# 1-Schematic_PedalBoard.net
KiCad netlist of a schematic drawn in EasyEDA
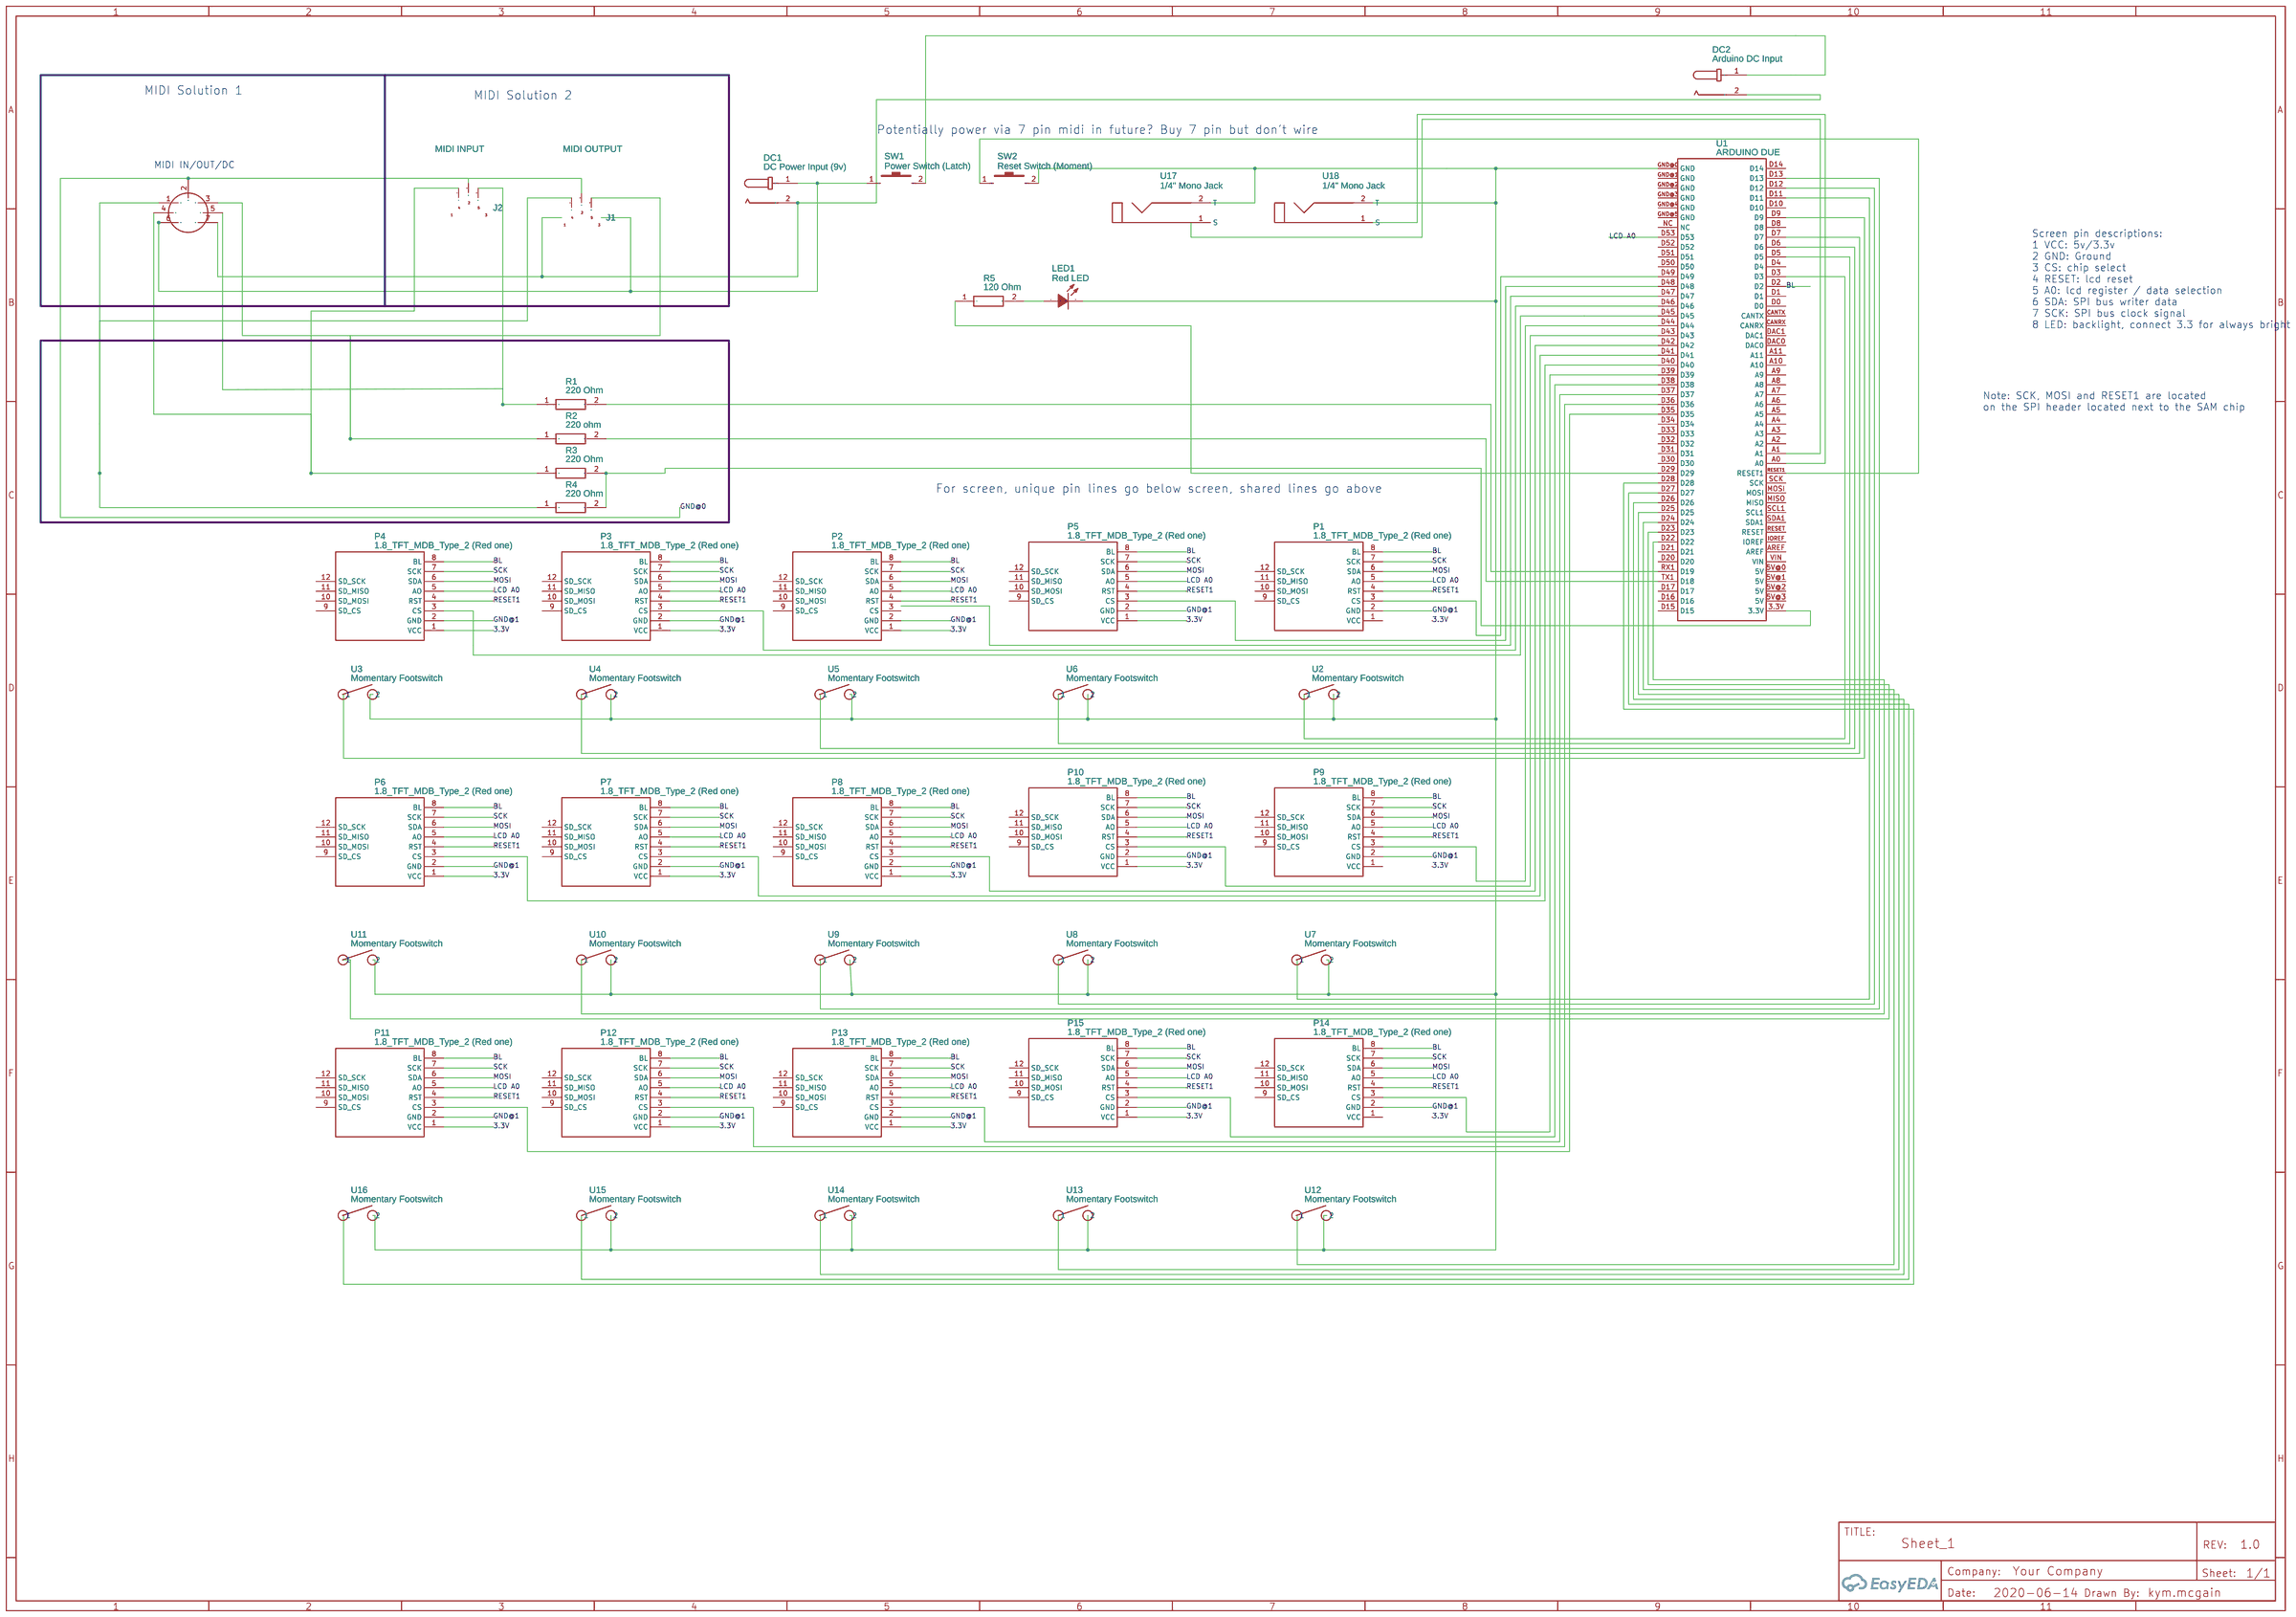
[diagram p0: Pedalboard]
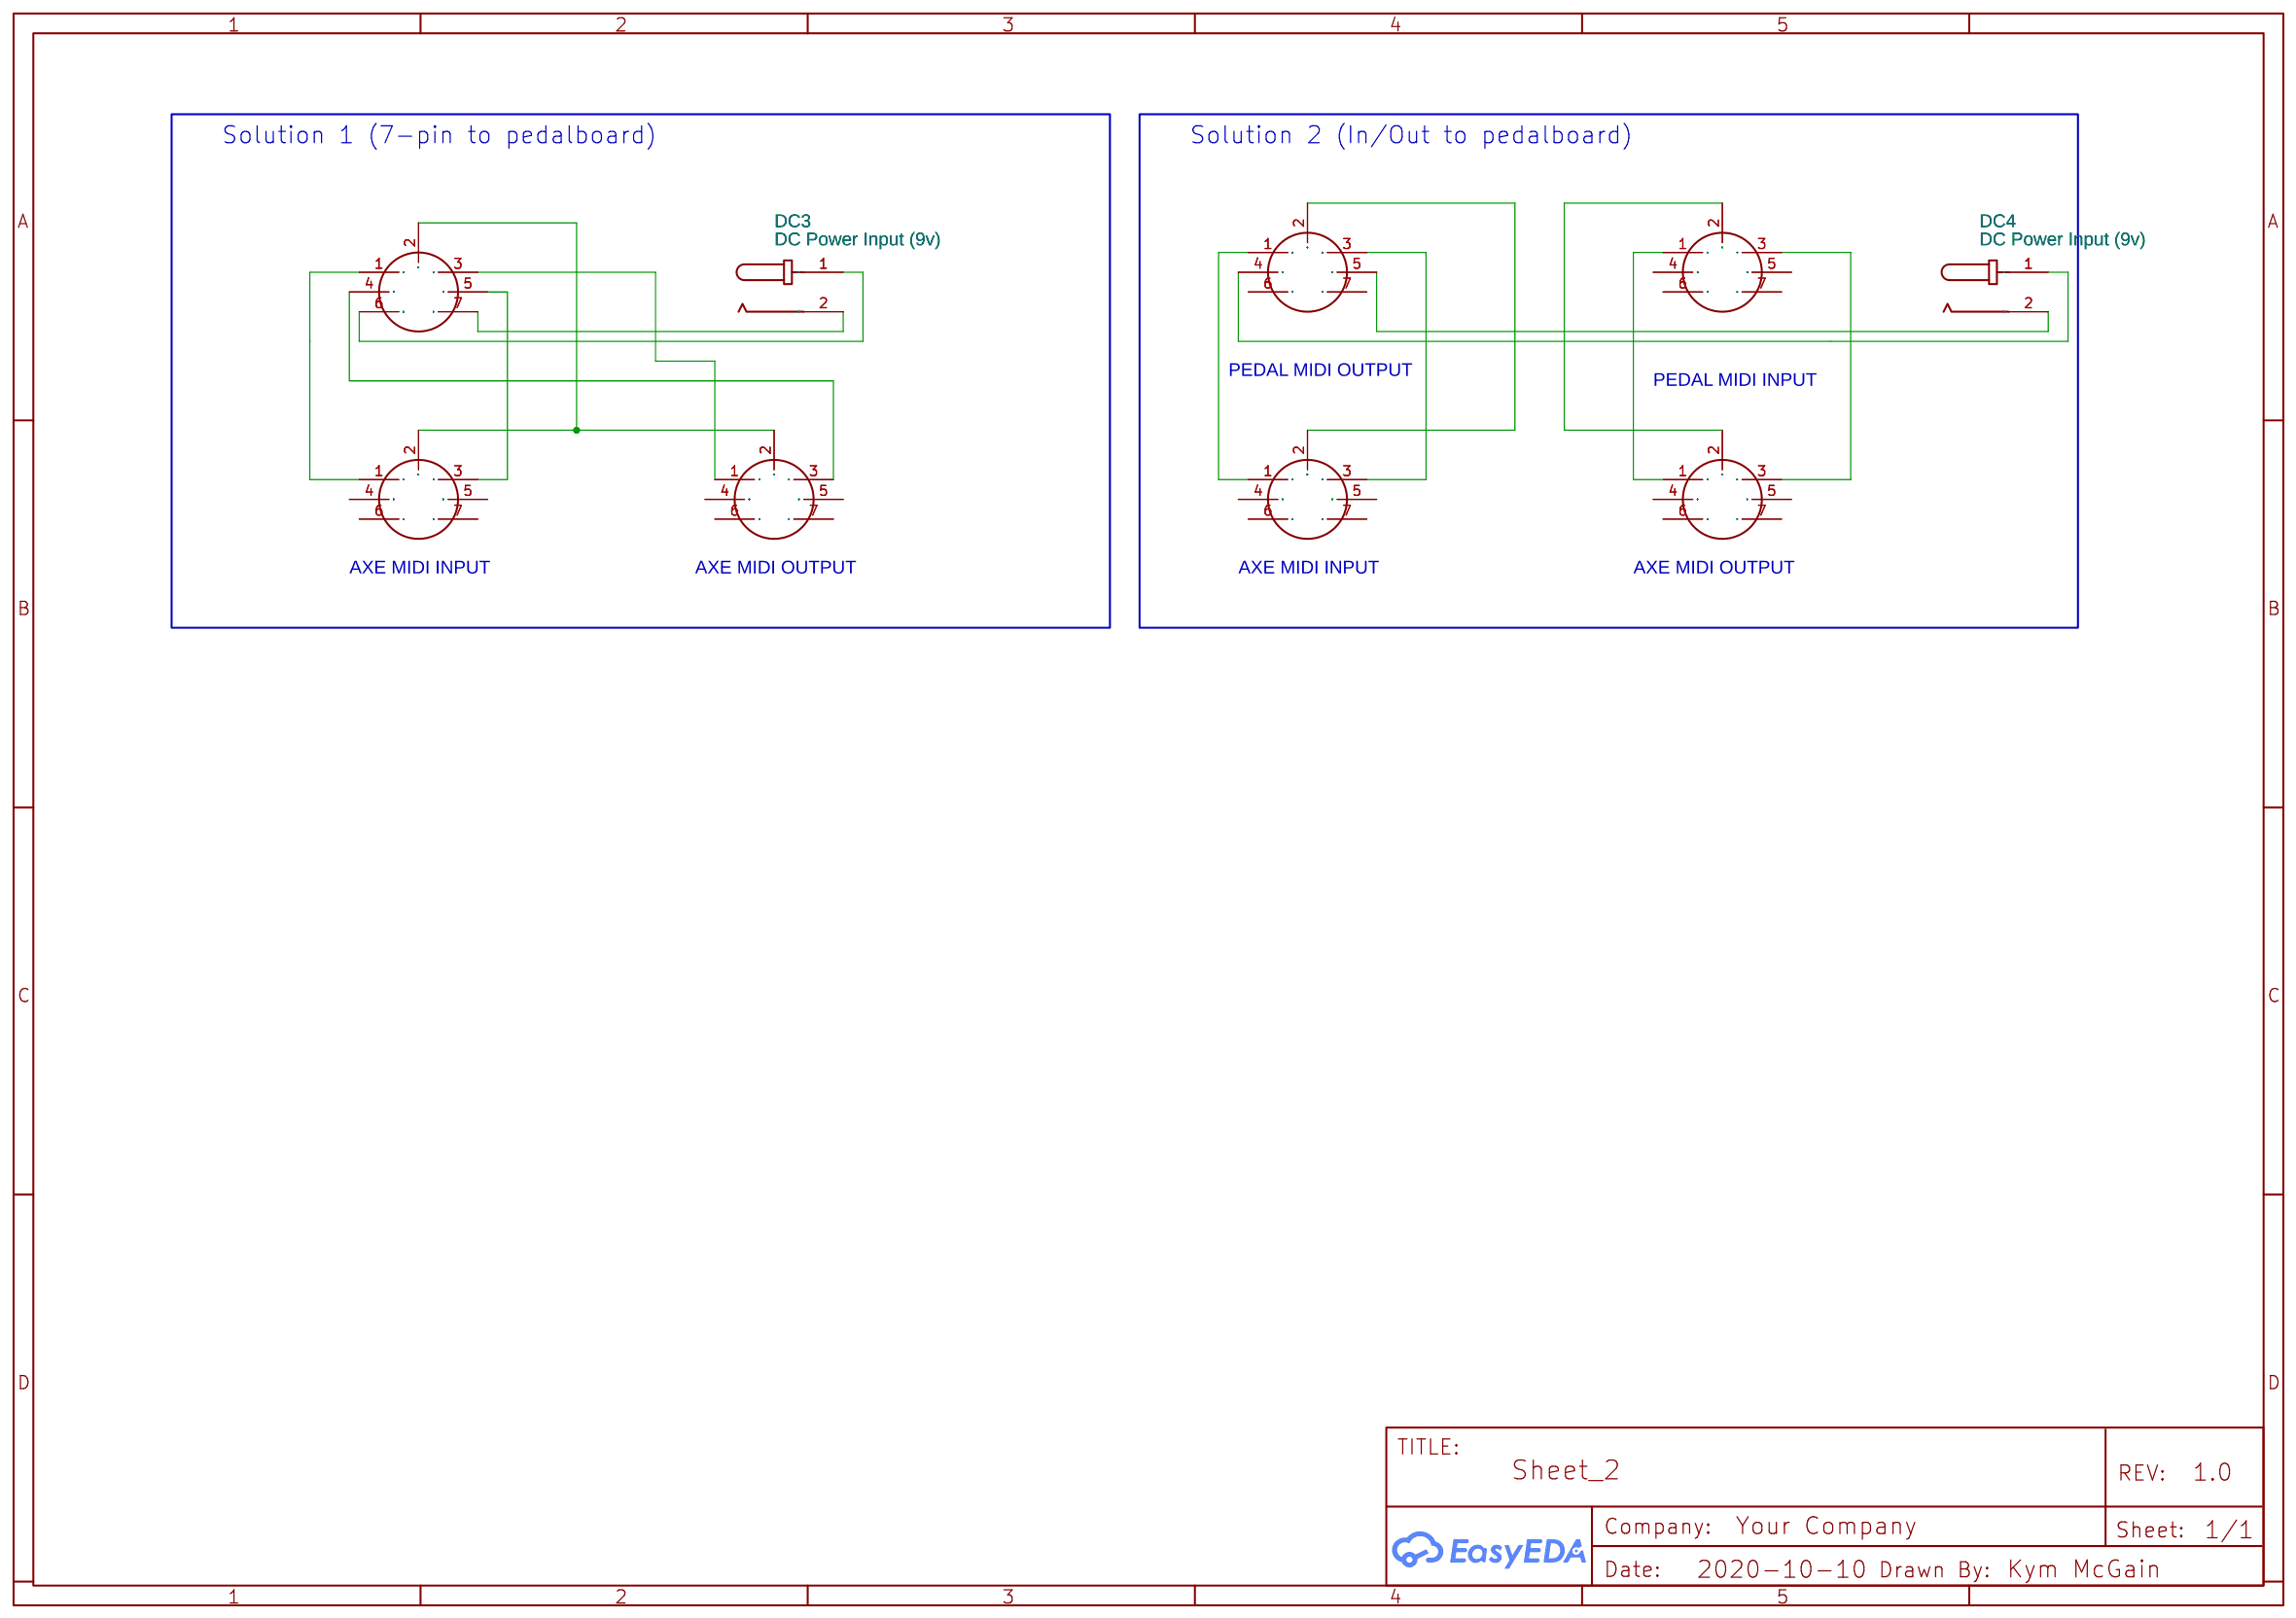
[diagram p1: MidiBox]

(export (version "E")
  (design (tool "Eeschema 10.0.6"))
  (components
    (comp (ref "DC1")
      (value "DC Power Input (9v)")
      (fields
        (field (name "BOM_Manufacturer Part") "DC-047B-13A")
        (field (name "BOM_Supplier Part") "C145923")
      )
      (libsource (lib "") (part "DC-047B-13A"))
    )
    (comp (ref "DC2")
      (value "Arduino DC Input")
      (fields
        (field (name "BOM_Manufacturer Part") "DC-047B-13A")
        (field (name "BOM_Supplier Part") "C145923")
      )
      (libsource (lib "") (part "DC-047B-13A"))
    )
    (comp (ref "J1") (value "MIDI OUTPUT") (libsource (lib "") (part "MIDI")))
    (comp (ref "J2") (value "MIDI INPUT") (libsource (lib "") (part "MIDI")))
    (comp (ref "LED1")
      (value "Red LED")
      (fields
        (field (name "BOM_Manufacturer Part") "KT-1206Red LED")
        (field (name "BOM_Supplier Part") "C49018")
      )
      (libsource (lib "") (part "KT-1206Red LED"))
    )
    (comp (ref "P1")
      (value "1.8_TFT_MDB_Type_2 (Red one)")
      (fields (field (name "BOM_Supplier Part") "undefined"))
      (libsource (lib "") (part "1.8_TFT_MDB_Type_2 (Red one)"))
    )
    (comp (ref "P2")
      (value "1.8_TFT_MDB_Type_2 (Red one)")
      (fields (field (name "BOM_Supplier Part") "undefined"))
      (libsource (lib "") (part "1.8_TFT_MDB_Type_2 (Red one)"))
    )
    (comp (ref "P3")
      (value "1.8_TFT_MDB_Type_2 (Red one)")
      (fields (field (name "BOM_Supplier Part") "undefined"))
      (libsource (lib "") (part "1.8_TFT_MDB_Type_2 (Red one)"))
    )
    (comp (ref "P4")
      (value "1.8_TFT_MDB_Type_2 (Red one)")
      (fields (field (name "BOM_Supplier Part") "undefined"))
      (libsource (lib "") (part "1.8_TFT_MDB_Type_2 (Red one)"))
    )
    (comp (ref "P5")
      (value "1.8_TFT_MDB_Type_2 (Red one)")
      (fields (field (name "BOM_Supplier Part") "undefined"))
      (libsource (lib "") (part "1.8_TFT_MDB_Type_2 (Red one)"))
    )
    (comp (ref "P6")
      (value "1.8_TFT_MDB_Type_2 (Red one)")
      (fields (field (name "BOM_Supplier Part") "undefined"))
      (libsource (lib "") (part "1.8_TFT_MDB_Type_2 (Red one)"))
    )
    (comp (ref "P7")
      (value "1.8_TFT_MDB_Type_2 (Red one)")
      (fields (field (name "BOM_Supplier Part") "undefined"))
      (libsource (lib "") (part "1.8_TFT_MDB_Type_2 (Red one)"))
    )
    (comp (ref "P8")
      (value "1.8_TFT_MDB_Type_2 (Red one)")
      (fields (field (name "BOM_Supplier Part") "undefined"))
      (libsource (lib "") (part "1.8_TFT_MDB_Type_2 (Red one)"))
    )
    (comp (ref "P9")
      (value "1.8_TFT_MDB_Type_2 (Red one)")
      (fields (field (name "BOM_Supplier Part") "undefined"))
      (libsource (lib "") (part "1.8_TFT_MDB_Type_2 (Red one)"))
    )
    (comp (ref "P10")
      (value "1.8_TFT_MDB_Type_2 (Red one)")
      (fields (field (name "BOM_Supplier Part") "undefined"))
      (libsource (lib "") (part "1.8_TFT_MDB_Type_2 (Red one)"))
    )
    (comp (ref "P11")
      (value "1.8_TFT_MDB_Type_2 (Red one)")
      (fields (field (name "BOM_Supplier Part") "undefined"))
      (libsource (lib "") (part "1.8_TFT_MDB_Type_2 (Red one)"))
    )
    (comp (ref "P12")
      (value "1.8_TFT_MDB_Type_2 (Red one)")
      (fields (field (name "BOM_Supplier Part") "undefined"))
      (libsource (lib "") (part "1.8_TFT_MDB_Type_2 (Red one)"))
    )
    (comp (ref "P13")
      (value "1.8_TFT_MDB_Type_2 (Red one)")
      (fields (field (name "BOM_Supplier Part") "undefined"))
      (libsource (lib "") (part "1.8_TFT_MDB_Type_2 (Red one)"))
    )
    (comp (ref "P14")
      (value "1.8_TFT_MDB_Type_2 (Red one)")
      (fields (field (name "BOM_Supplier Part") "undefined"))
      (libsource (lib "") (part "1.8_TFT_MDB_Type_2 (Red one)"))
    )
    (comp (ref "P15")
      (value "1.8_TFT_MDB_Type_2 (Red one)")
      (fields (field (name "BOM_Supplier Part") "undefined"))
      (libsource (lib "") (part "1.8_TFT_MDB_Type_2 (Red one)"))
    )
    (comp (ref "R1")
      (value "220 Ohm")
      (libsource (lib "") (part "200 Ohms ±5% 1W Chip Resistor 2512 CRCW2512200RJNTG"))
    )
    (comp (ref "R2")
      (value "220 ohm")
      (libsource (lib "") (part "200 Ohms ±5% 1W Chip Resistor 2512 CRCW2512200RJNTG"))
    )
    (comp (ref "R3")
      (value "220 Ohm")
      (libsource (lib "") (part "200 Ohms ±5% 1W Chip Resistor 2512 CRCW2512200RJNTG"))
    )
    (comp (ref "R4")
      (value "220 Ohm")
      (libsource (lib "") (part "200 Ohms ±5% 1W Chip Resistor 2512 CRCW2512200RJNTG"))
    )
    (comp (ref "R5")
      (value "120 Ohm")
      (libsource (lib "") (part "200 Ohms ±5% 1W Chip Resistor 2512 CRCW2512200RJNTG"))
    )
    (comp (ref "SW1")
      (value "Power Switch (Latch)")
      (fields
        (field (name "BOM_Manufacturer Part") "Switch3x4x2")
        (field (name "BOM_Supplier Part") "C26638")
      )
      (libsource (lib "") (part "Switch3x4x2"))
    )
    (comp (ref "SW2")
      (value "Reset Switch (Moment)")
      (fields
        (field (name "BOM_Manufacturer Part") "Switch3x4x2")
        (field (name "BOM_Supplier Part") "C26638")
      )
      (libsource (lib "") (part "Switch3x4x2"))
    )
    (comp (ref "U1") (value "ARDUINO DUE") (libsource (lib "") (part "ARDUINO DUE")))
    (comp (ref "U2") (value "Momentary Footswitch") (libsource (lib "") (part "Momentary Footswitch")))
    (comp (ref "U3") (value "Momentary Footswitch") (libsource (lib "") (part "Momentary Footswitch_1")))
    (comp (ref "U4") (value "Momentary Footswitch") (libsource (lib "") (part "Momentary Footswitch")))
    (comp (ref "U5") (value "Momentary Footswitch") (libsource (lib "") (part "Momentary Footswitch_1")))
    (comp (ref "U6") (value "Momentary Footswitch") (libsource (lib "") (part "Momentary Footswitch")))
    (comp (ref "U7") (value "Momentary Footswitch") (libsource (lib "") (part "Momentary Footswitch_1")))
    (comp (ref "U8") (value "Momentary Footswitch") (libsource (lib "") (part "Momentary Footswitch")))
    (comp (ref "U9") (value "Momentary Footswitch") (libsource (lib "") (part "Momentary Footswitch_1")))
    (comp (ref "U10") (value "Momentary Footswitch") (libsource (lib "") (part "Momentary Footswitch")))
    (comp (ref "U11") (value "Momentary Footswitch") (libsource (lib "") (part "Momentary Footswitch_1")))
    (comp (ref "U12") (value "Momentary Footswitch") (libsource (lib "") (part "Momentary Footswitch_1")))
    (comp (ref "U13") (value "Momentary Footswitch") (libsource (lib "") (part "Momentary Footswitch")))
    (comp (ref "U14") (value "Momentary Footswitch") (libsource (lib "") (part "Momentary Footswitch_1")))
    (comp (ref "U15") (value "Momentary Footswitch") (libsource (lib "") (part "Momentary Footswitch")))
    (comp (ref "U16") (value "Momentary Footswitch") (libsource (lib "") (part "Momentary Footswitch_1")))
    (comp (ref "U17")
      (value "1/4\" Mono Jack")
      (fields
        (field (name "BOM_Manufacturer Part") "NYS2162-U")
        (field (name "BOM_Supplier Part") "568-NYS2162-U")
      )
      (libsource (lib "") (part "1/4{dblquote} Mono Jack"))
    )
    (comp (ref "U18")
      (value "1/4\" Mono Jack")
      (fields
        (field (name "BOM_Manufacturer Part") "NYS2162-U")
        (field (name "BOM_Supplier Part") "568-NYS2162-U")
      )
      (libsource (lib "") (part "1/4{dblquote} Mono Jack"))
    )
    (comp (ref "U19") (value "DIN 45329") (libsource (lib "") (part "DIN 45329")))
    (comp (ref "DC3")
      (value "DC Power Input (9v)")
      (fields
        (field (name "BOM_Manufacturer Part") "DC-047B-13A")
        (field (name "BOM_Supplier Part") "C145923")
      )
      (libsource (lib "") (part "DC-047B-13A"))
    )
    (comp (ref "DC4")
      (value "DC Power Input (9v)")
      (fields
        (field (name "BOM_Manufacturer Part") "DC-047B-13A")
        (field (name "BOM_Supplier Part") "C145923")
      )
      (libsource (lib "") (part "DC-047B-13A"))
    )
    (comp (ref "U20") (value "DIN 45329") (libsource (lib "") (part "DIN 45329")))
    (comp (ref "U21") (value "DIN 45329") (libsource (lib "") (part "DIN 45329")))
    (comp (ref "U22") (value "DIN 45329") (libsource (lib "") (part "DIN 45329")))
    (comp (ref "U23") (value "DIN 45329") (libsource (lib "") (part "DIN 45329")))
    (comp (ref "U24") (value "DIN 45329") (libsource (lib "") (part "DIN 45329")))
    (comp (ref "U25") (value "DIN 45329") (libsource (lib "") (part "DIN 45329")))
    (comp (ref "U26") (value "DIN 45329") (libsource (lib "") (part "DIN 45329")))
  )
  (nets
    (net (code "1") (name "3.3V") (class "Default")
      (node (ref "P10") (pin "1") (pinfunction "VCC_1") (pintype "unspecified"))
      (node (ref "P11") (pin "1") (pinfunction "VCC_1") (pintype "unspecified"))
      (node (ref "P12") (pin "1") (pinfunction "VCC_1") (pintype "unspecified"))
      (node (ref "P13") (pin "1") (pinfunction "VCC_1") (pintype "unspecified"))
      (node (ref "P15") (pin "1") (pinfunction "VCC_1") (pintype "unspecified"))
      (node (ref "P2") (pin "1") (pinfunction "VCC_1") (pintype "unspecified"))
      (node (ref "P3") (pin "1") (pinfunction "VCC_1") (pintype "unspecified"))
      (node (ref "P4") (pin "1") (pinfunction "VCC_1") (pintype "unspecified"))
      (node (ref "P5") (pin "1") (pinfunction "VCC_1") (pintype "unspecified"))
      (node (ref "P6") (pin "1") (pinfunction "VCC_1") (pintype "unspecified"))
      (node (ref "P7") (pin "1") (pinfunction "VCC_1") (pintype "unspecified"))
      (node (ref "P8") (pin "1") (pinfunction "VCC_1") (pintype "unspecified"))
    )
    (net (code "2") (name "BL") (class "Default")
      (node (ref "P1") (pin "8") (pinfunction "BL_8") (pintype "unspecified"))
      (node (ref "P10") (pin "8") (pinfunction "BL_8") (pintype "unspecified"))
      (node (ref "P11") (pin "8") (pinfunction "BL_8") (pintype "unspecified"))
      (node (ref "P12") (pin "8") (pinfunction "BL_8") (pintype "unspecified"))
      (node (ref "P13") (pin "8") (pinfunction "BL_8") (pintype "unspecified"))
      (node (ref "P14") (pin "8") (pinfunction "BL_8") (pintype "unspecified"))
      (node (ref "P15") (pin "8") (pinfunction "BL_8") (pintype "unspecified"))
      (node (ref "P2") (pin "8") (pinfunction "BL_8") (pintype "unspecified"))
      (node (ref "P3") (pin "8") (pinfunction "BL_8") (pintype "unspecified"))
      (node (ref "P4") (pin "8") (pinfunction "BL_8") (pintype "unspecified"))
      (node (ref "P5") (pin "8") (pinfunction "BL_8") (pintype "unspecified"))
      (node (ref "P6") (pin "8") (pinfunction "BL_8") (pintype "unspecified"))
      (node (ref "P7") (pin "8") (pinfunction "BL_8") (pintype "unspecified"))
      (node (ref "P8") (pin "8") (pinfunction "BL_8") (pintype "unspecified"))
      (node (ref "P9") (pin "8") (pinfunction "BL_8") (pintype "unspecified"))
      (node (ref "U1") (pin "D2") (pinfunction "D2_D2") (pintype "unspecified"))
    )
    (net (code "3") (name "GND@0") (class "Default")
      (node (ref "J1") (pin "R") (pinfunction "2_R") (pintype "bidirectional"))
      (node (ref "J2") (pin "R") (pinfunction "2_R") (pintype "bidirectional"))
      (node (ref "U19") (pin "2") (pinfunction "6_2") (pintype "unspecified"))
    )
    (net (code "4") (name "GND@1") (class "Default")
      (node (ref "P1") (pin "2") (pinfunction "GND_2") (pintype "unspecified"))
      (node (ref "P10") (pin "2") (pinfunction "GND_2") (pintype "unspecified"))
      (node (ref "P11") (pin "2") (pinfunction "GND_2") (pintype "unspecified"))
      (node (ref "P12") (pin "2") (pinfunction "GND_2") (pintype "unspecified"))
      (node (ref "P13") (pin "2") (pinfunction "GND_2") (pintype "unspecified"))
      (node (ref "P14") (pin "2") (pinfunction "GND_2") (pintype "unspecified"))
      (node (ref "P15") (pin "2") (pinfunction "GND_2") (pintype "unspecified"))
      (node (ref "P2") (pin "2") (pinfunction "GND_2") (pintype "unspecified"))
      (node (ref "P3") (pin "2") (pinfunction "GND_2") (pintype "unspecified"))
      (node (ref "P4") (pin "2") (pinfunction "GND_2") (pintype "unspecified"))
      (node (ref "P5") (pin "2") (pinfunction "GND_2") (pintype "unspecified"))
      (node (ref "P6") (pin "2") (pinfunction "GND_2") (pintype "unspecified"))
      (node (ref "P7") (pin "2") (pinfunction "GND_2") (pintype "unspecified"))
      (node (ref "P8") (pin "2") (pinfunction "GND_2") (pintype "unspecified"))
      (node (ref "P9") (pin "2") (pinfunction "GND_2") (pintype "unspecified"))
    )
    (net (code "5") (name "LCD A0") (class "Default")
      (node (ref "P1") (pin "5") (pinfunction "AO_5") (pintype "unspecified"))
      (node (ref "P10") (pin "5") (pinfunction "AO_5") (pintype "unspecified"))
      (node (ref "P11") (pin "5") (pinfunction "AO_5") (pintype "unspecified"))
      (node (ref "P12") (pin "5") (pinfunction "AO_5") (pintype "unspecified"))
      (node (ref "P13") (pin "5") (pinfunction "AO_5") (pintype "unspecified"))
      (node (ref "P14") (pin "5") (pinfunction "AO_5") (pintype "unspecified"))
      (node (ref "P15") (pin "5") (pinfunction "AO_5") (pintype "unspecified"))
      (node (ref "P2") (pin "5") (pinfunction "AO_5") (pintype "unspecified"))
      (node (ref "P3") (pin "5") (pinfunction "AO_5") (pintype "unspecified"))
      (node (ref "P4") (pin "5") (pinfunction "AO_5") (pintype "unspecified"))
      (node (ref "P5") (pin "5") (pinfunction "AO_5") (pintype "unspecified"))
      (node (ref "P6") (pin "5") (pinfunction "AO_5") (pintype "unspecified"))
      (node (ref "P7") (pin "5") (pinfunction "AO_5") (pintype "unspecified"))
      (node (ref "P8") (pin "5") (pinfunction "AO_5") (pintype "unspecified"))
      (node (ref "P9") (pin "5") (pinfunction "AO_5") (pintype "unspecified"))
      (node (ref "U1") (pin "D53") (pinfunction "D53_D53") (pintype "unspecified"))
    )
    (net (code "6") (name "MOSI") (class "Default")
      (node (ref "P1") (pin "6") (pinfunction "SDA_6") (pintype "unspecified"))
      (node (ref "P10") (pin "6") (pinfunction "SDA_6") (pintype "unspecified"))
      (node (ref "P11") (pin "6") (pinfunction "SDA_6") (pintype "unspecified"))
      (node (ref "P12") (pin "6") (pinfunction "SDA_6") (pintype "unspecified"))
      (node (ref "P13") (pin "6") (pinfunction "SDA_6") (pintype "unspecified"))
      (node (ref "P14") (pin "6") (pinfunction "SDA_6") (pintype "unspecified"))
      (node (ref "P15") (pin "6") (pinfunction "SDA_6") (pintype "unspecified"))
      (node (ref "P2") (pin "6") (pinfunction "SDA_6") (pintype "unspecified"))
      (node (ref "P3") (pin "6") (pinfunction "SDA_6") (pintype "unspecified"))
      (node (ref "P4") (pin "6") (pinfunction "SDA_6") (pintype "unspecified"))
      (node (ref "P5") (pin "6") (pinfunction "SDA_6") (pintype "unspecified"))
      (node (ref "P6") (pin "6") (pinfunction "SDA_6") (pintype "unspecified"))
      (node (ref "P7") (pin "6") (pinfunction "SDA_6") (pintype "unspecified"))
      (node (ref "P8") (pin "6") (pinfunction "SDA_6") (pintype "unspecified"))
      (node (ref "P9") (pin "6") (pinfunction "SDA_6") (pintype "unspecified"))
    )
    (net (code "7") (name "Net-(DC1-Pad1)") (class "Default")
      (node (ref "DC1") (pin "1") (pinfunction "1_1") (pintype "unspecified"))
      (node (ref "SW1") (pin "1") (pinfunction "1_1") (pintype "input"))
      (node (ref "U19") (pin "6") (pinfunction "6_6") (pintype "unspecified"))
    )
    (net (code "8") (name "Net-(DC1-Pad2)") (class "Default")
      (node (ref "DC1") (pin "2") (pinfunction "2_2") (pintype "unspecified"))
      (node (ref "DC2") (pin "2") (pinfunction "2_2") (pintype "unspecified"))
      (node (ref "U19") (pin "7") (pinfunction "6_7") (pintype "unspecified"))
    )
    (net (code "9") (name "Net-(DC2-Pad1)") (class "Default")
      (node (ref "DC2") (pin "1") (pinfunction "1_1") (pintype "unspecified"))
      (node (ref "SW1") (pin "2") (pinfunction "2_2") (pintype "input"))
    )
    (net (code "10") (name "Net-(DC3-Pad1)") (class "Default")
      (node (ref "DC3") (pin "1") (pinfunction "1_1") (pintype "unspecified"))
      (node (ref "U20") (pin "6") (pinfunction "6_6") (pintype "unspecified"))
    )
    (net (code "11") (name "Net-(DC3-Pad2)") (class "Default")
      (node (ref "DC3") (pin "2") (pinfunction "2_2") (pintype "unspecified"))
      (node (ref "U20") (pin "7") (pinfunction "6_7") (pintype "unspecified"))
    )
    (net (code "12") (name "Net-(DC4-Pad1)") (class "Default")
      (node (ref "DC4") (pin "1") (pinfunction "1_1") (pintype "unspecified"))
      (node (ref "U25") (pin "4") (pinfunction "6_4") (pintype "unspecified"))
    )
    (net (code "13") (name "Net-(DC4-Pad2)") (class "Default")
      (node (ref "DC4") (pin "2") (pinfunction "2_2") (pintype "unspecified"))
      (node (ref "U25") (pin "5") (pinfunction "6_5") (pintype "unspecified"))
    )
    (net (code "14") (name "Net-(J1-4)") (class "Default")
      (node (ref "J1") (pin "T") (pinfunction "4_T") (pintype "bidirectional"))
      (node (ref "R4") (pin "1") (pinfunction "1_1") (pintype "bidirectional"))
      (node (ref "U19") (pin "1") (pinfunction "6_1") (pintype "unspecified"))
    )
    (net (code "15") (name "Net-(J1-5)") (class "Default")
      (node (ref "J1") (pin "S") (pinfunction "5_S") (pintype "bidirectional"))
      (node (ref "R2") (pin "1") (pinfunction "1_1") (pintype "bidirectional"))
      (node (ref "U19") (pin "3") (pinfunction "6_3") (pintype "unspecified"))
    )
    (net (code "16") (name "Net-(J2-4)") (class "Default")
      (node (ref "J2") (pin "T") (pinfunction "4_T") (pintype "bidirectional"))
      (node (ref "R3") (pin "1") (pinfunction "1_1") (pintype "bidirectional"))
      (node (ref "U19") (pin "4") (pinfunction "6_4") (pintype "unspecified"))
    )
    (net (code "17") (name "Net-(J2-5)") (class "Default")
      (node (ref "J2") (pin "S") (pinfunction "5_S") (pintype "bidirectional"))
      (node (ref "R1") (pin "1") (pinfunction "1_1") (pintype "bidirectional"))
      (node (ref "U19") (pin "5") (pinfunction "6_5") (pintype "unspecified"))
    )
    (net (code "18") (name "Net-(LED1-A)") (class "Default")
      (node (ref "LED1") (pin "1") (pinfunction "A_1") (pintype "unspecified"))
      (node (ref "R5") (pin "2") (pinfunction "2_2") (pintype "bidirectional"))
    )
    (net (code "19") (name "Net-(LED1-K)") (class "Default")
      (node (ref "LED1") (pin "2") (pinfunction "K_2") (pintype "unspecified"))
      (node (ref "SW2") (pin "2") (pinfunction "2_2") (pintype "input"))
      (node (ref "U1") (pin "GND@0") (pinfunction "GND_GND@0") (pintype "unspecified"))
      (node (ref "U10") (pin "2") (pinfunction "2_2") (pintype "unspecified"))
      (node (ref "U11") (pin "2") (pinfunction "2_2") (pintype "unspecified"))
      (node (ref "U12") (pin "2") (pinfunction "2_2") (pintype "unspecified"))
      (node (ref "U13") (pin "2") (pinfunction "2_2") (pintype "unspecified"))
      (node (ref "U14") (pin "2") (pinfunction "2_2") (pintype "unspecified"))
      (node (ref "U15") (pin "2") (pinfunction "2_2") (pintype "unspecified"))
      (node (ref "U16") (pin "2") (pinfunction "2_2") (pintype "unspecified"))
      (node (ref "U17") (pin "2") (pinfunction "T_2") (pintype "unspecified"))
      (node (ref "U18") (pin "2") (pinfunction "T_2") (pintype "unspecified"))
      (node (ref "U2") (pin "2") (pinfunction "2_2") (pintype "unspecified"))
      (node (ref "U3") (pin "2") (pinfunction "2_2") (pintype "unspecified"))
      (node (ref "U4") (pin "2") (pinfunction "2_2") (pintype "unspecified"))
      (node (ref "U5") (pin "2") (pinfunction "2_2") (pintype "unspecified"))
      (node (ref "U6") (pin "2") (pinfunction "2_2") (pintype "unspecified"))
      (node (ref "U7") (pin "2") (pinfunction "2_2") (pintype "unspecified"))
      (node (ref "U8") (pin "2") (pinfunction "2_2") (pintype "unspecified"))
      (node (ref "U9") (pin "2") (pinfunction "2_2") (pintype "unspecified"))
    )
    (net (code "20") (name "Net-(P1-CS)") (class "Default")
      (node (ref "P1") (pin "3") (pinfunction "CS_3") (pintype "unspecified"))
      (node (ref "U1") (pin "D49") (pinfunction "D49_D49") (pintype "unspecified"))
    )
    (net (code "21") (name "Net-(P3-CS)") (class "Default")
      (node (ref "P3") (pin "3") (pinfunction "CS_3") (pintype "unspecified"))
      (node (ref "U1") (pin "D46") (pinfunction "D46_D46") (pintype "unspecified"))
    )
    (net (code "22") (name "Net-(P4-CS)") (class "Default")
      (node (ref "P4") (pin "3") (pinfunction "CS_3") (pintype "unspecified"))
      (node (ref "U1") (pin "D45") (pinfunction "D45_D45") (pintype "unspecified"))
    )
    (net (code "23") (name "Net-(P5-CS)") (class "Default")
      (node (ref "P5") (pin "3") (pinfunction "CS_3") (pintype "unspecified"))
      (node (ref "U1") (pin "D48") (pinfunction "D48_D48") (pintype "unspecified"))
    )
    (net (code "24") (name "Net-(P6-CS)") (class "Default")
      (node (ref "P6") (pin "3") (pinfunction "CS_3") (pintype "unspecified"))
      (node (ref "U1") (pin "D40") (pinfunction "D40_D40") (pintype "unspecified"))
    )
    (net (code "25") (name "Net-(P7-CS)") (class "Default")
      (node (ref "P7") (pin "3") (pinfunction "CS_3") (pintype "unspecified"))
      (node (ref "U1") (pin "D41") (pinfunction "D41_D41") (pintype "unspecified"))
    )
    (net (code "26") (name "Net-(P8-CS)") (class "Default")
      (node (ref "P8") (pin "3") (pinfunction "CS_3") (pintype "unspecified"))
      (node (ref "U1") (pin "D42") (pinfunction "D42_D42") (pintype "unspecified"))
    )
    (net (code "27") (name "Net-(P9-CS)") (class "Default")
      (node (ref "P9") (pin "3") (pinfunction "CS_3") (pintype "unspecified"))
      (node (ref "U1") (pin "D44") (pinfunction "D44_D44") (pintype "unspecified"))
    )
    (net (code "28") (name "Net-(P10-CS)") (class "Default")
      (node (ref "P10") (pin "3") (pinfunction "CS_3") (pintype "unspecified"))
      (node (ref "U1") (pin "D43") (pinfunction "D43_D43") (pintype "unspecified"))
    )
    (net (code "29") (name "Net-(P11-CS)") (class "Default")
      (node (ref "P11") (pin "3") (pinfunction "CS_3") (pintype "unspecified"))
      (node (ref "U1") (pin "D35") (pinfunction "D35_D35") (pintype "unspecified"))
    )
    (net (code "30") (name "Net-(P12-CS)") (class "Default")
      (node (ref "P12") (pin "3") (pinfunction "CS_3") (pintype "unspecified"))
      (node (ref "U1") (pin "D36") (pinfunction "D36_D36") (pintype "unspecified"))
    )
    (net (code "31") (name "Net-(P13-CS)") (class "Default")
      (node (ref "P13") (pin "3") (pinfunction "CS_3") (pintype "unspecified"))
      (node (ref "U1") (pin "D37") (pinfunction "D37_D37") (pintype "unspecified"))
    )
    (net (code "32") (name "Net-(P14-CS)") (class "Default")
      (node (ref "P14") (pin "3") (pinfunction "CS_3") (pintype "unspecified"))
      (node (ref "U1") (pin "D39") (pinfunction "D39_D39") (pintype "unspecified"))
    )
    (net (code "33") (name "Net-(P15-CS)") (class "Default")
      (node (ref "P15") (pin "3") (pinfunction "CS_3") (pintype "unspecified"))
      (node (ref "U1") (pin "D38") (pinfunction "D38_D38") (pintype "unspecified"))
    )
    (net (code "34") (name "Net-(R3-Pad2)") (class "Default")
      (node (ref "R3") (pin "2") (pinfunction "2_2") (pintype "bidirectional"))
      (node (ref "R4") (pin "2") (pinfunction "2_2") (pintype "bidirectional"))
      (node (ref "U1") (pin "3.3V") (pinfunction "3.3V_3.3V") (pintype "unspecified"))
    )
    (net (code "35") (name "Net-(R5-Pad1)") (class "Default")
      (node (ref "R5") (pin "1") (pinfunction "1_1") (pintype "bidirectional"))
      (node (ref "U1") (pin "D29") (pinfunction "D29_D29") (pintype "unspecified"))
    )
    (net (code "36") (name "Net-(SW2-Pad1)") (class "Default")
      (node (ref "SW2") (pin "1") (pinfunction "1_1") (pintype "input"))
      (node (ref "U1") (pin "RESET1") (pinfunction "RESET1_RESET1") (pintype "unspecified"))
    )
    (net (code "37") (name "Net-(U1-D18)") (class "Default")
      (node (ref "R2") (pin "2") (pinfunction "2_2") (pintype "bidirectional"))
      (node (ref "U1") (pin "TX1") (pinfunction "D18_TX1") (pintype "unspecified"))
    )
    (net (code "38") (name "Net-(U1-D19)") (class "Default")
      (node (ref "R1") (pin "2") (pinfunction "2_2") (pintype "bidirectional"))
      (node (ref "U1") (pin "RX1") (pinfunction "D19_RX1") (pintype "unspecified"))
    )
    (net (code "39") (name "Net-(U1-PadD3)") (class "Default")
      (node (ref "U1") (pin "D3") (pinfunction "D3_D3") (pintype "unspecified"))
      (node (ref "U2") (pin "1") (pinfunction "1_1") (pintype "unspecified"))
    )
    (net (code "40") (name "Net-(U1-PadD5)") (class "Default")
      (node (ref "U1") (pin "D5") (pinfunction "D5_D5") (pintype "unspecified"))
      (node (ref "U6") (pin "1") (pinfunction "1_1") (pintype "unspecified"))
    )
    (net (code "41") (name "Net-(U1-PadD6)") (class "Default")
      (node (ref "U1") (pin "D6") (pinfunction "D6_D6") (pintype "unspecified"))
      (node (ref "U5") (pin "1") (pinfunction "1_1") (pintype "unspecified"))
    )
    (net (code "42") (name "Net-(U1-PadD7)") (class "Default")
      (node (ref "U1") (pin "D7") (pinfunction "D7_D7") (pintype "unspecified"))
      (node (ref "U4") (pin "1") (pinfunction "1_1") (pintype "unspecified"))
    )
    (net (code "43") (name "Net-(U1-PadD9)") (class "Default")
      (node (ref "U1") (pin "D9") (pinfunction "D9_D9") (pintype "unspecified"))
      (node (ref "U3") (pin "1") (pinfunction "1_1") (pintype "unspecified"))
    )
    (net (code "44") (name "Net-(U1-PadD11)") (class "Default")
      (node (ref "U1") (pin "D11") (pinfunction "D11_D11") (pintype "unspecified"))
      (node (ref "U7") (pin "1") (pinfunction "1_1") (pintype "unspecified"))
    )
    (net (code "45") (name "Net-(U1-PadD12)") (class "Default")
      (node (ref "U1") (pin "D12") (pinfunction "D12_D12") (pintype "unspecified"))
      (node (ref "U8") (pin "1") (pinfunction "1_1") (pintype "unspecified"))
    )
    (net (code "46") (name "Net-(U1-PadD13)") (class "Default")
      (node (ref "U1") (pin "D13") (pinfunction "D13_D13") (pintype "unspecified"))
      (node (ref "U9") (pin "1") (pinfunction "1_1") (pintype "unspecified"))
    )
    (net (code "47") (name "Net-(U1-PadD22)") (class "Default")
      (node (ref "U1") (pin "D22") (pinfunction "D22_D22") (pintype "unspecified"))
      (node (ref "U10") (pin "1") (pinfunction "1_1") (pintype "unspecified"))
    )
    (net (code "48") (name "Net-(U1-PadD23)") (class "Default")
      (node (ref "U1") (pin "D23") (pinfunction "D23_D23") (pintype "unspecified"))
      (node (ref "U11") (pin "1") (pinfunction "1_1") (pintype "unspecified"))
    )
    (net (code "49") (name "Net-(U1-PadD24)") (class "Default")
      (node (ref "U1") (pin "D24") (pinfunction "D24_D24") (pintype "unspecified"))
      (node (ref "U12") (pin "1") (pinfunction "1_1") (pintype "unspecified"))
    )
    (net (code "50") (name "Net-(U1-PadD25)") (class "Default")
      (node (ref "U1") (pin "D25") (pinfunction "D25_D25") (pintype "unspecified"))
      (node (ref "U13") (pin "1") (pinfunction "1_1") (pintype "unspecified"))
    )
    (net (code "51") (name "Net-(U1-PadD26)") (class "Default")
      (node (ref "U1") (pin "D26") (pinfunction "D26_D26") (pintype "unspecified"))
      (node (ref "U14") (pin "1") (pinfunction "1_1") (pintype "unspecified"))
    )
    (net (code "52") (name "Net-(U1-PadD27)") (class "Default")
      (node (ref "U1") (pin "D27") (pinfunction "D27_D27") (pintype "unspecified"))
      (node (ref "U15") (pin "1") (pinfunction "1_1") (pintype "unspecified"))
    )
    (net (code "53") (name "Net-(U1-PadD28)") (class "Default")
      (node (ref "U1") (pin "D28") (pinfunction "D28_D28") (pintype "unspecified"))
      (node (ref "U16") (pin "1") (pinfunction "1_1") (pintype "unspecified"))
    )
    (net (code "54") (name "Net-(U17-S)") (class "Default")
      (node (ref "U1") (pin "A1") (pinfunction "A1_A1") (pintype "unspecified"))
      (node (ref "U17") (pin "1") (pinfunction "S_1") (pintype "unspecified"))
    )
    (net (code "55") (name "Net-(U18-S)") (class "Default")
      (node (ref "U1") (pin "A0") (pinfunction "A0_A0") (pintype "unspecified"))
      (node (ref "U18") (pin "1") (pinfunction "S_1") (pintype "unspecified"))
    )
    (net (code "56") (name "Net-(U20-6-Pad1)") (class "Default")
      (node (ref "U20") (pin "1") (pinfunction "6_1") (pintype "unspecified"))
      (node (ref "U22") (pin "1") (pinfunction "6_1") (pintype "unspecified"))
    )
    (net (code "57") (name "Net-(U20-6-Pad2)") (class "Default")
      (node (ref "U20") (pin "2") (pinfunction "6_2") (pintype "unspecified"))
      (node (ref "U21") (pin "2") (pinfunction "6_2") (pintype "unspecified"))
      (node (ref "U22") (pin "2") (pinfunction "6_2") (pintype "unspecified"))
    )
    (net (code "58") (name "Net-(U20-6-Pad3)") (class "Default")
      (node (ref "U20") (pin "3") (pinfunction "6_3") (pintype "unspecified"))
      (node (ref "U21") (pin "1") (pinfunction "6_1") (pintype "unspecified"))
    )
    (net (code "59") (name "Net-(U20-6-Pad4)") (class "Default")
      (node (ref "U20") (pin "4") (pinfunction "6_4") (pintype "unspecified"))
      (node (ref "U21") (pin "3") (pinfunction "6_3") (pintype "unspecified"))
    )
    (net (code "60") (name "Net-(U20-6-Pad5)") (class "Default")
      (node (ref "U20") (pin "5") (pinfunction "6_5") (pintype "unspecified"))
      (node (ref "U22") (pin "3") (pinfunction "6_3") (pintype "unspecified"))
    )
    (net (code "61") (name "Net-(U23-6-Pad1)") (class "Default")
      (node (ref "U23") (pin "1") (pinfunction "6_1") (pintype "unspecified"))
      (node (ref "U26") (pin "1") (pinfunction "6_1") (pintype "unspecified"))
    )
    (net (code "62") (name "Net-(U23-6-Pad2)") (class "Default")
      (node (ref "U23") (pin "2") (pinfunction "6_2") (pintype "unspecified"))
      (node (ref "U26") (pin "2") (pinfunction "6_2") (pintype "unspecified"))
    )
    (net (code "63") (name "Net-(U23-6-Pad3)") (class "Default")
      (node (ref "U23") (pin "3") (pinfunction "6_3") (pintype "unspecified"))
      (node (ref "U26") (pin "3") (pinfunction "6_3") (pintype "unspecified"))
    )
    (net (code "64") (name "Net-(U24-6-Pad1)") (class "Default")
      (node (ref "U24") (pin "1") (pinfunction "6_1") (pintype "unspecified"))
      (node (ref "U25") (pin "1") (pinfunction "6_1") (pintype "unspecified"))
    )
    (net (code "65") (name "Net-(U24-6-Pad2)") (class "Default")
      (node (ref "U24") (pin "2") (pinfunction "6_2") (pintype "unspecified"))
      (node (ref "U25") (pin "2") (pinfunction "6_2") (pintype "unspecified"))
    )
    (net (code "66") (name "Net-(U24-6-Pad3)") (class "Default")
      (node (ref "U24") (pin "3") (pinfunction "6_3") (pintype "unspecified"))
      (node (ref "U25") (pin "3") (pinfunction "6_3") (pintype "unspecified"))
    )
    (net (code "67") (name "RESET1") (class "Default")
      (node (ref "P1") (pin "4") (pinfunction "RST_4") (pintype "unspecified"))
      (node (ref "P10") (pin "4") (pinfunction "RST_4") (pintype "unspecified"))
      (node (ref "P11") (pin "4") (pinfunction "RST_4") (pintype "unspecified"))
      (node (ref "P12") (pin "4") (pinfunction "RST_4") (pintype "unspecified"))
      (node (ref "P13") (pin "4") (pinfunction "RST_4") (pintype "unspecified"))
      (node (ref "P14") (pin "4") (pinfunction "RST_4") (pintype "unspecified"))
      (node (ref "P15") (pin "4") (pinfunction "RST_4") (pintype "unspecified"))
      (node (ref "P2") (pin "4") (pinfunction "RST_4") (pintype "unspecified"))
      (node (ref "P3") (pin "4") (pinfunction "RST_4") (pintype "unspecified"))
      (node (ref "P4") (pin "4") (pinfunction "RST_4") (pintype "unspecified"))
      (node (ref "P5") (pin "4") (pinfunction "RST_4") (pintype "unspecified"))
      (node (ref "P6") (pin "4") (pinfunction "RST_4") (pintype "unspecified"))
      (node (ref "P7") (pin "4") (pinfunction "RST_4") (pintype "unspecified"))
      (node (ref "P8") (pin "4") (pinfunction "RST_4") (pintype "unspecified"))
      (node (ref "P9") (pin "4") (pinfunction "RST_4") (pintype "unspecified"))
    )
    (net (code "68") (name "SCK") (class "Default")
      (node (ref "P1") (pin "7") (pinfunction "SCK_7") (pintype "unspecified"))
      (node (ref "P10") (pin "7") (pinfunction "SCK_7") (pintype "unspecified"))
      (node (ref "P11") (pin "7") (pinfunction "SCK_7") (pintype "unspecified"))
      (node (ref "P12") (pin "7") (pinfunction "SCK_7") (pintype "unspecified"))
      (node (ref "P13") (pin "7") (pinfunction "SCK_7") (pintype "unspecified"))
      (node (ref "P14") (pin "7") (pinfunction "SCK_7") (pintype "unspecified"))
      (node (ref "P15") (pin "7") (pinfunction "SCK_7") (pintype "unspecified"))
      (node (ref "P2") (pin "7") (pinfunction "SCK_7") (pintype "unspecified"))
      (node (ref "P3") (pin "7") (pinfunction "SCK_7") (pintype "unspecified"))
      (node (ref "P4") (pin "7") (pinfunction "SCK_7") (pintype "unspecified"))
      (node (ref "P5") (pin "7") (pinfunction "SCK_7") (pintype "unspecified"))
      (node (ref "P6") (pin "7") (pinfunction "SCK_7") (pintype "unspecified"))
      (node (ref "P7") (pin "7") (pinfunction "SCK_7") (pintype "unspecified"))
      (node (ref "P8") (pin "7") (pinfunction "SCK_7") (pintype "unspecified"))
      (node (ref "P9") (pin "7") (pinfunction "SCK_7") (pintype "unspecified"))
    )
    (net (code "69") (name "unconnected-(P1-SD_CS-Pad9)") (class "Default")
      (node (ref "P1") (pin "9") (pinfunction "SD_CS_9") (pintype "unspecified"))
    )
    (net (code "70") (name "unconnected-(P1-SD_MISO-Pad11)") (class "Default")
      (node (ref "P1") (pin "11") (pinfunction "SD_MISO_11") (pintype "unspecified"))
    )
    (net (code "71") (name "unconnected-(P1-SD_MOSI-Pad10)") (class "Default")
      (node (ref "P1") (pin "10") (pinfunction "SD_MOSI_10") (pintype "unspecified"))
    )
    (net (code "72") (name "unconnected-(P1-SD_SCK-Pad12)") (class "Default")
      (node (ref "P1") (pin "12") (pinfunction "SD_SCK_12") (pintype "unspecified"))
    )
    (net (code "73") (name "unconnected-(P1-VCC-Pad1)") (class "Default")
      (node (ref "P1") (pin "1") (pinfunction "VCC_1") (pintype "unspecified"))
    )
    (net (code "74") (name "unconnected-(P2-CS-Pad3)") (class "Default")
      (node (ref "P2") (pin "3") (pinfunction "CS_3") (pintype "unspecified"))
    )
    (net (code "75") (name "unconnected-(P2-SD_CS-Pad9)") (class "Default")
      (node (ref "P2") (pin "9") (pinfunction "SD_CS_9") (pintype "unspecified"))
    )
    (net (code "76") (name "unconnected-(P2-SD_MISO-Pad11)") (class "Default")
      (node (ref "P2") (pin "11") (pinfunction "SD_MISO_11") (pintype "unspecified"))
    )
    (net (code "77") (name "unconnected-(P2-SD_MOSI-Pad10)") (class "Default")
      (node (ref "P2") (pin "10") (pinfunction "SD_MOSI_10") (pintype "unspecified"))
    )
    (net (code "78") (name "unconnected-(P2-SD_SCK-Pad12)") (class "Default")
      (node (ref "P2") (pin "12") (pinfunction "SD_SCK_12") (pintype "unspecified"))
    )
    (net (code "79") (name "unconnected-(P3-SD_CS-Pad9)") (class "Default")
      (node (ref "P3") (pin "9") (pinfunction "SD_CS_9") (pintype "unspecified"))
    )
    (net (code "80") (name "unconnected-(P3-SD_MISO-Pad11)") (class "Default")
      (node (ref "P3") (pin "11") (pinfunction "SD_MISO_11") (pintype "unspecified"))
    )
    (net (code "81") (name "unconnected-(P3-SD_MOSI-Pad10)") (class "Default")
      (node (ref "P3") (pin "10") (pinfunction "SD_MOSI_10") (pintype "unspecified"))
    )
    (net (code "82") (name "unconnected-(P3-SD_SCK-Pad12)") (class "Default")
      (node (ref "P3") (pin "12") (pinfunction "SD_SCK_12") (pintype "unspecified"))
    )
    (net (code "83") (name "unconnected-(P4-SD_CS-Pad9)") (class "Default")
      (node (ref "P4") (pin "9") (pinfunction "SD_CS_9") (pintype "unspecified"))
    )
    (net (code "84") (name "unconnected-(P4-SD_MISO-Pad11)") (class "Default")
      (node (ref "P4") (pin "11") (pinfunction "SD_MISO_11") (pintype "unspecified"))
    )
    (net (code "85") (name "unconnected-(P4-SD_MOSI-Pad10)") (class "Default")
      (node (ref "P4") (pin "10") (pinfunction "SD_MOSI_10") (pintype "unspecified"))
    )
    (net (code "86") (name "unconnected-(P4-SD_SCK-Pad12)") (class "Default")
      (node (ref "P4") (pin "12") (pinfunction "SD_SCK_12") (pintype "unspecified"))
    )
    (net (code "87") (name "unconnected-(P5-SD_CS-Pad9)") (class "Default")
      (node (ref "P5") (pin "9") (pinfunction "SD_CS_9") (pintype "unspecified"))
    )
    (net (code "88") (name "unconnected-(P5-SD_MISO-Pad11)") (class "Default")
      (node (ref "P5") (pin "11") (pinfunction "SD_MISO_11") (pintype "unspecified"))
    )
    (net (code "89") (name "unconnected-(P5-SD_MOSI-Pad10)") (class "Default")
      (node (ref "P5") (pin "10") (pinfunction "SD_MOSI_10") (pintype "unspecified"))
    )
    (net (code "90") (name "unconnected-(P5-SD_SCK-Pad12)") (class "Default")
      (node (ref "P5") (pin "12") (pinfunction "SD_SCK_12") (pintype "unspecified"))
    )
    (net (code "91") (name "unconnected-(P6-SD_CS-Pad9)") (class "Default")
      (node (ref "P6") (pin "9") (pinfunction "SD_CS_9") (pintype "unspecified"))
    )
    (net (code "92") (name "unconnected-(P6-SD_MISO-Pad11)") (class "Default")
      (node (ref "P6") (pin "11") (pinfunction "SD_MISO_11") (pintype "unspecified"))
    )
    (net (code "93") (name "unconnected-(P6-SD_MOSI-Pad10)") (class "Default")
      (node (ref "P6") (pin "10") (pinfunction "SD_MOSI_10") (pintype "unspecified"))
    )
    (net (code "94") (name "unconnected-(P6-SD_SCK-Pad12)") (class "Default")
      (node (ref "P6") (pin "12") (pinfunction "SD_SCK_12") (pintype "unspecified"))
    )
    (net (code "95") (name "unconnected-(P7-SD_CS-Pad9)") (class "Default")
      (node (ref "P7") (pin "9") (pinfunction "SD_CS_9") (pintype "unspecified"))
    )
    (net (code "96") (name "unconnected-(P7-SD_MISO-Pad11)") (class "Default")
      (node (ref "P7") (pin "11") (pinfunction "SD_MISO_11") (pintype "unspecified"))
    )
    (net (code "97") (name "unconnected-(P7-SD_MOSI-Pad10)") (class "Default")
      (node (ref "P7") (pin "10") (pinfunction "SD_MOSI_10") (pintype "unspecified"))
    )
    (net (code "98") (name "unconnected-(P7-SD_SCK-Pad12)") (class "Default")
      (node (ref "P7") (pin "12") (pinfunction "SD_SCK_12") (pintype "unspecified"))
    )
    (net (code "99") (name "unconnected-(P8-SD_CS-Pad9)") (class "Default")
      (node (ref "P8") (pin "9") (pinfunction "SD_CS_9") (pintype "unspecified"))
    )
    (net (code "100") (name "unconnected-(P8-SD_MISO-Pad11)") (class "Default")
      (node (ref "P8") (pin "11") (pinfunction "SD_MISO_11") (pintype "unspecified"))
    )
    (net (code "101") (name "unconnected-(P8-SD_MOSI-Pad10)") (class "Default")
      (node (ref "P8") (pin "10") (pinfunction "SD_MOSI_10") (pintype "unspecified"))
    )
    (net (code "102") (name "unconnected-(P8-SD_SCK-Pad12)") (class "Default")
      (node (ref "P8") (pin "12") (pinfunction "SD_SCK_12") (pintype "unspecified"))
    )
    (net (code "103") (name "unconnected-(P9-SD_CS-Pad9)") (class "Default")
      (node (ref "P9") (pin "9") (pinfunction "SD_CS_9") (pintype "unspecified"))
    )
    (net (code "104") (name "unconnected-(P9-SD_MISO-Pad11)") (class "Default")
      (node (ref "P9") (pin "11") (pinfunction "SD_MISO_11") (pintype "unspecified"))
    )
    (net (code "105") (name "unconnected-(P9-SD_MOSI-Pad10)") (class "Default")
      (node (ref "P9") (pin "10") (pinfunction "SD_MOSI_10") (pintype "unspecified"))
    )
    (net (code "106") (name "unconnected-(P9-SD_SCK-Pad12)") (class "Default")
      (node (ref "P9") (pin "12") (pinfunction "SD_SCK_12") (pintype "unspecified"))
    )
    (net (code "107") (name "unconnected-(P9-VCC-Pad1)") (class "Default")
      (node (ref "P9") (pin "1") (pinfunction "VCC_1") (pintype "unspecified"))
    )
    (net (code "108") (name "unconnected-(P10-SD_CS-Pad9)") (class "Default")
      (node (ref "P10") (pin "9") (pinfunction "SD_CS_9") (pintype "unspecified"))
    )
    (net (code "109") (name "unconnected-(P10-SD_MISO-Pad11)") (class "Default")
      (node (ref "P10") (pin "11") (pinfunction "SD_MISO_11") (pintype "unspecified"))
    )
    (net (code "110") (name "unconnected-(P10-SD_MOSI-Pad10)") (class "Default")
      (node (ref "P10") (pin "10") (pinfunction "SD_MOSI_10") (pintype "unspecified"))
    )
    (net (code "111") (name "unconnected-(P10-SD_SCK-Pad12)") (class "Default")
      (node (ref "P10") (pin "12") (pinfunction "SD_SCK_12") (pintype "unspecified"))
    )
    (net (code "112") (name "unconnected-(P11-SD_CS-Pad9)") (class "Default")
      (node (ref "P11") (pin "9") (pinfunction "SD_CS_9") (pintype "unspecified"))
    )
    (net (code "113") (name "unconnected-(P11-SD_MISO-Pad11)") (class "Default")
      (node (ref "P11") (pin "11") (pinfunction "SD_MISO_11") (pintype "unspecified"))
    )
    (net (code "114") (name "unconnected-(P11-SD_MOSI-Pad10)") (class "Default")
      (node (ref "P11") (pin "10") (pinfunction "SD_MOSI_10") (pintype "unspecified"))
    )
    (net (code "115") (name "unconnected-(P11-SD_SCK-Pad12)") (class "Default")
      (node (ref "P11") (pin "12") (pinfunction "SD_SCK_12") (pintype "unspecified"))
    )
    (net (code "116") (name "unconnected-(P12-SD_CS-Pad9)") (class "Default")
      (node (ref "P12") (pin "9") (pinfunction "SD_CS_9") (pintype "unspecified"))
    )
    (net (code "117") (name "unconnected-(P12-SD_MISO-Pad11)") (class "Default")
      (node (ref "P12") (pin "11") (pinfunction "SD_MISO_11") (pintype "unspecified"))
    )
    (net (code "118") (name "unconnected-(P12-SD_MOSI-Pad10)") (class "Default")
      (node (ref "P12") (pin "10") (pinfunction "SD_MOSI_10") (pintype "unspecified"))
    )
    (net (code "119") (name "unconnected-(P12-SD_SCK-Pad12)") (class "Default")
      (node (ref "P12") (pin "12") (pinfunction "SD_SCK_12") (pintype "unspecified"))
    )
    (net (code "120") (name "unconnected-(P13-SD_CS-Pad9)") (class "Default")
      (node (ref "P13") (pin "9") (pinfunction "SD_CS_9") (pintype "unspecified"))
    )
    (net (code "121") (name "unconnected-(P13-SD_MISO-Pad11)") (class "Default")
      (node (ref "P13") (pin "11") (pinfunction "SD_MISO_11") (pintype "unspecified"))
    )
    (net (code "122") (name "unconnected-(P13-SD_MOSI-Pad10)") (class "Default")
      (node (ref "P13") (pin "10") (pinfunction "SD_MOSI_10") (pintype "unspecified"))
    )
    (net (code "123") (name "unconnected-(P13-SD_SCK-Pad12)") (class "Default")
      (node (ref "P13") (pin "12") (pinfunction "SD_SCK_12") (pintype "unspecified"))
    )
    (net (code "124") (name "unconnected-(P14-SD_CS-Pad9)") (class "Default")
      (node (ref "P14") (pin "9") (pinfunction "SD_CS_9") (pintype "unspecified"))
    )
    (net (code "125") (name "unconnected-(P14-SD_MISO-Pad11)") (class "Default")
      (node (ref "P14") (pin "11") (pinfunction "SD_MISO_11") (pintype "unspecified"))
    )
    (net (code "126") (name "unconnected-(P14-SD_MOSI-Pad10)") (class "Default")
      (node (ref "P14") (pin "10") (pinfunction "SD_MOSI_10") (pintype "unspecified"))
    )
    (net (code "127") (name "unconnected-(P14-SD_SCK-Pad12)") (class "Default")
      (node (ref "P14") (pin "12") (pinfunction "SD_SCK_12") (pintype "unspecified"))
    )
    (net (code "128") (name "unconnected-(P14-VCC-Pad1)") (class "Default")
      (node (ref "P14") (pin "1") (pinfunction "VCC_1") (pintype "unspecified"))
    )
    (net (code "129") (name "unconnected-(P15-SD_CS-Pad9)") (class "Default")
      (node (ref "P15") (pin "9") (pinfunction "SD_CS_9") (pintype "unspecified"))
    )
    (net (code "130") (name "unconnected-(P15-SD_MISO-Pad11)") (class "Default")
      (node (ref "P15") (pin "11") (pinfunction "SD_MISO_11") (pintype "unspecified"))
    )
    (net (code "131") (name "unconnected-(P15-SD_MOSI-Pad10)") (class "Default")
      (node (ref "P15") (pin "10") (pinfunction "SD_MOSI_10") (pintype "unspecified"))
    )
    (net (code "132") (name "unconnected-(P15-SD_SCK-Pad12)") (class "Default")
      (node (ref "P15") (pin "12") (pinfunction "SD_SCK_12") (pintype "unspecified"))
    )
    (net (code "133") (name "unconnected-(U1-5V-Pad5V@0)") (class "Default")
      (node (ref "U1") (pin "5V@0") (pinfunction "5V_5V@0") (pintype "unspecified"))
    )
    (net (code "134") (name "unconnected-(U1-5V-Pad5V@1)") (class "Default")
      (node (ref "U1") (pin "5V@1") (pinfunction "5V_5V@1") (pintype "unspecified"))
    )
    (net (code "135") (name "unconnected-(U1-5V-Pad5V@2)") (class "Default")
      (node (ref "U1") (pin "5V@2") (pinfunction "5V_5V@2") (pintype "unspecified"))
    )
    (net (code "136") (name "unconnected-(U1-5V-Pad5V@3)") (class "Default")
      (node (ref "U1") (pin "5V@3") (pinfunction "5V_5V@3") (pintype "unspecified"))
    )
    (net (code "137") (name "unconnected-(U1-GND-PadGND@1)") (class "Default")
      (node (ref "U1") (pin "GND@1") (pinfunction "GND_GND@1") (pintype "unspecified"))
    )
    (net (code "138") (name "unconnected-(U1-GND-PadGND@2)") (class "Default")
      (node (ref "U1") (pin "GND@2") (pinfunction "GND_GND@2") (pintype "unspecified"))
    )
    (net (code "139") (name "unconnected-(U1-GND-PadGND@3)") (class "Default")
      (node (ref "U1") (pin "GND@3") (pinfunction "GND_GND@3") (pintype "unspecified"))
    )
    (net (code "140") (name "unconnected-(U1-GND-PadGND@4)") (class "Default")
      (node (ref "U1") (pin "GND@4") (pinfunction "GND_GND@4") (pintype "unspecified"))
    )
    (net (code "141") (name "unconnected-(U1-GND-PadGND@5)") (class "Default")
      (node (ref "U1") (pin "GND@5") (pinfunction "GND_GND@5") (pintype "unspecified"))
    )
    (net (code "142") (name "unconnected-(U1-PadA2)") (class "Default")
      (node (ref "U1") (pin "A2") (pinfunction "A2_A2") (pintype "unspecified"))
    )
    (net (code "143") (name "unconnected-(U1-PadA3)") (class "Default")
      (node (ref "U1") (pin "A3") (pinfunction "A3_A3") (pintype "unspecified"))
    )
    (net (code "144") (name "unconnected-(U1-PadA4)") (class "Default")
      (node (ref "U1") (pin "A4") (pinfunction "A4_A4") (pintype "unspecified"))
    )
    (net (code "145") (name "unconnected-(U1-PadA5)") (class "Default")
      (node (ref "U1") (pin "A5") (pinfunction "A5_A5") (pintype "unspecified"))
    )
    (net (code "146") (name "unconnected-(U1-PadA6)") (class "Default")
      (node (ref "U1") (pin "A6") (pinfunction "A6_A6") (pintype "unspecified"))
    )
    (net (code "147") (name "unconnected-(U1-PadA7)") (class "Default")
      (node (ref "U1") (pin "A7") (pinfunction "A7_A7") (pintype "unspecified"))
    )
    (net (code "148") (name "unconnected-(U1-PadA8)") (class "Default")
      (node (ref "U1") (pin "A8") (pinfunction "A8_A8") (pintype "unspecified"))
    )
    (net (code "149") (name "unconnected-(U1-PadA9)") (class "Default")
      (node (ref "U1") (pin "A9") (pinfunction "A9_A9") (pintype "unspecified"))
    )
    (net (code "150") (name "unconnected-(U1-PadA10)") (class "Default")
      (node (ref "U1") (pin "A10") (pinfunction "A10_A10") (pintype "unspecified"))
    )
    (net (code "151") (name "unconnected-(U1-PadA11)") (class "Default")
      (node (ref "U1") (pin "A11") (pinfunction "A11_A11") (pintype "unspecified"))
    )
    (net (code "152") (name "unconnected-(U1-PadAREF)") (class "Default")
      (node (ref "U1") (pin "AREF") (pinfunction "AREF_AREF") (pintype "unspecified"))
    )
    (net (code "153") (name "unconnected-(U1-PadCANRX)") (class "Default")
      (node (ref "U1") (pin "CANRX") (pinfunction "CANRX_CANRX") (pintype "unspecified"))
    )
    (net (code "154") (name "unconnected-(U1-PadCANTX)") (class "Default")
      (node (ref "U1") (pin "CANTX") (pinfunction "CANTX_CANTX") (pintype "unspecified"))
    )
    (net (code "155") (name "unconnected-(U1-PadD0)") (class "Default")
      (node (ref "U1") (pin "D0") (pinfunction "D0_D0") (pintype "unspecified"))
    )
    (net (code "156") (name "unconnected-(U1-PadD1)") (class "Default")
      (node (ref "U1") (pin "D1") (pinfunction "D1_D1") (pintype "unspecified"))
    )
    (net (code "157") (name "unconnected-(U1-PadD4)") (class "Default")
      (node (ref "U1") (pin "D4") (pinfunction "D4_D4") (pintype "unspecified"))
    )
    (net (code "158") (name "unconnected-(U1-PadD8)") (class "Default")
      (node (ref "U1") (pin "D8") (pinfunction "D8_D8") (pintype "unspecified"))
    )
    (net (code "159") (name "unconnected-(U1-PadD10)") (class "Default")
      (node (ref "U1") (pin "D10") (pinfunction "D10_D10") (pintype "unspecified"))
    )
    (net (code "160") (name "unconnected-(U1-PadD14)") (class "Default")
      (node (ref "U1") (pin "D14") (pinfunction "D14_D14") (pintype "unspecified"))
    )
    (net (code "161") (name "unconnected-(U1-PadD15)") (class "Default")
      (node (ref "U1") (pin "D15") (pinfunction "D15_D15") (pintype "unspecified"))
    )
    (net (code "162") (name "unconnected-(U1-PadD16)") (class "Default")
      (node (ref "U1") (pin "D16") (pinfunction "D16_D16") (pintype "unspecified"))
    )
    (net (code "163") (name "unconnected-(U1-PadD17)") (class "Default")
      (node (ref "U1") (pin "D17") (pinfunction "D17_D17") (pintype "unspecified"))
    )
    (net (code "164") (name "unconnected-(U1-PadD20)") (class "Default")
      (node (ref "U1") (pin "D20") (pinfunction "D20_D20") (pintype "unspecified"))
    )
    (net (code "165") (name "unconnected-(U1-PadD21)") (class "Default")
      (node (ref "U1") (pin "D21") (pinfunction "D21_D21") (pintype "unspecified"))
    )
    (net (code "166") (name "unconnected-(U1-PadD30)") (class "Default")
      (node (ref "U1") (pin "D30") (pinfunction "D30_D30") (pintype "unspecified"))
    )
    (net (code "167") (name "unconnected-(U1-PadD31)") (class "Default")
      (node (ref "U1") (pin "D31") (pinfunction "D31_D31") (pintype "unspecified"))
    )
    (net (code "168") (name "unconnected-(U1-PadD32)") (class "Default")
      (node (ref "U1") (pin "D32") (pinfunction "D32_D32") (pintype "unspecified"))
    )
    (net (code "169") (name "unconnected-(U1-PadD33)") (class "Default")
      (node (ref "U1") (pin "D33") (pinfunction "D33_D33") (pintype "unspecified"))
    )
    (net (code "170") (name "unconnected-(U1-PadD34)") (class "Default")
      (node (ref "U1") (pin "D34") (pinfunction "D34_D34") (pintype "unspecified"))
    )
    (net (code "171") (name "unconnected-(U1-PadD47)") (class "Default")
      (node (ref "U1") (pin "D47") (pinfunction "D47_D47") (pintype "unspecified"))
    )
    (net (code "172") (name "unconnected-(U1-PadD50)") (class "Default")
      (node (ref "U1") (pin "D50") (pinfunction "D50_D50") (pintype "unspecified"))
    )
    (net (code "173") (name "unconnected-(U1-PadD51)") (class "Default")
      (node (ref "U1") (pin "D51") (pinfunction "D51_D51") (pintype "unspecified"))
    )
    (net (code "174") (name "unconnected-(U1-PadD52)") (class "Default")
      (node (ref "U1") (pin "D52") (pinfunction "D52_D52") (pintype "unspecified"))
    )
    (net (code "175") (name "unconnected-(U1-PadDAC0)") (class "Default")
      (node (ref "U1") (pin "DAC0") (pinfunction "DAC0_DAC0") (pintype "unspecified"))
    )
    (net (code "176") (name "unconnected-(U1-PadDAC1)") (class "Default")
      (node (ref "U1") (pin "DAC1") (pinfunction "DAC1_DAC1") (pintype "unspecified"))
    )
    (net (code "177") (name "unconnected-(U1-PadIOREF)") (class "Default")
      (node (ref "U1") (pin "IOREF") (pinfunction "IOREF_IOREF") (pintype "unspecified"))
    )
    (net (code "178") (name "unconnected-(U1-PadMISO)") (class "Default")
      (node (ref "U1") (pin "MISO") (pinfunction "MISO_MISO") (pintype "unspecified"))
    )
    (net (code "179") (name "unconnected-(U1-PadMOSI)") (class "Default")
      (node (ref "U1") (pin "MOSI") (pinfunction "MOSI_MOSI") (pintype "unspecified"))
    )
    (net (code "180") (name "unconnected-(U1-PadNC)") (class "Default")
      (node (ref "U1") (pin "NC") (pinfunction "NC_NC") (pintype "unspecified"))
    )
    (net (code "181") (name "unconnected-(U1-PadRESET)") (class "Default")
      (node (ref "U1") (pin "RESET") (pinfunction "RESET_RESET") (pintype "unspecified"))
    )
    (net (code "182") (name "unconnected-(U1-PadSCK)") (class "Default")
      (node (ref "U1") (pin "SCK") (pinfunction "SCK_SCK") (pintype "unspecified"))
    )
    (net (code "183") (name "unconnected-(U1-PadSCL1)") (class "Default")
      (node (ref "U1") (pin "SCL1") (pinfunction "SCL1_SCL1") (pintype "unspecified"))
    )
    (net (code "184") (name "unconnected-(U1-PadSDA1)") (class "Default")
      (node (ref "U1") (pin "SDA1") (pinfunction "SDA1_SDA1") (pintype "unspecified"))
    )
    (net (code "185") (name "unconnected-(U1-PadVIN)") (class "Default")
      (node (ref "U1") (pin "VIN") (pinfunction "VIN_VIN") (pintype "unspecified"))
    )
    (net (code "186") (name "unconnected-(U21-6-Pad4)") (class "Default")
      (node (ref "U21") (pin "4") (pinfunction "6_4") (pintype "unspecified"))
    )
    (net (code "187") (name "unconnected-(U21-6-Pad5)") (class "Default")
      (node (ref "U21") (pin "5") (pinfunction "6_5") (pintype "unspecified"))
    )
    (net (code "188") (name "unconnected-(U21-6-Pad7)") (class "Default")
      (node (ref "U21") (pin "7") (pinfunction "6_7") (pintype "unspecified"))
    )
    (net (code "189") (name "unconnected-(U21-Pad6)") (class "Default")
      (node (ref "U21") (pin "6") (pinfunction "6_6") (pintype "unspecified"))
    )
    (net (code "190") (name "unconnected-(U22-6-Pad4)") (class "Default")
      (node (ref "U22") (pin "4") (pinfunction "6_4") (pintype "unspecified"))
    )
    (net (code "191") (name "unconnected-(U22-6-Pad5)") (class "Default")
      (node (ref "U22") (pin "5") (pinfunction "6_5") (pintype "unspecified"))
    )
    (net (code "192") (name "unconnected-(U22-6-Pad7)") (class "Default")
      (node (ref "U22") (pin "7") (pinfunction "6_7") (pintype "unspecified"))
    )
    (net (code "193") (name "unconnected-(U22-Pad6)") (class "Default")
      (node (ref "U22") (pin "6") (pinfunction "6_6") (pintype "unspecified"))
    )
    (net (code "194") (name "unconnected-(U23-6-Pad4)") (class "Default")
      (node (ref "U23") (pin "4") (pinfunction "6_4") (pintype "unspecified"))
    )
    (net (code "195") (name "unconnected-(U23-6-Pad5)") (class "Default")
      (node (ref "U23") (pin "5") (pinfunction "6_5") (pintype "unspecified"))
    )
    (net (code "196") (name "unconnected-(U23-6-Pad7)") (class "Default")
      (node (ref "U23") (pin "7") (pinfunction "6_7") (pintype "unspecified"))
    )
    (net (code "197") (name "unconnected-(U23-Pad6)") (class "Default")
      (node (ref "U23") (pin "6") (pinfunction "6_6") (pintype "unspecified"))
    )
    (net (code "198") (name "unconnected-(U24-6-Pad4)") (class "Default")
      (node (ref "U24") (pin "4") (pinfunction "6_4") (pintype "unspecified"))
    )
    (net (code "199") (name "unconnected-(U24-6-Pad5)") (class "Default")
      (node (ref "U24") (pin "5") (pinfunction "6_5") (pintype "unspecified"))
    )
    (net (code "200") (name "unconnected-(U24-6-Pad7)") (class "Default")
      (node (ref "U24") (pin "7") (pinfunction "6_7") (pintype "unspecified"))
    )
    (net (code "201") (name "unconnected-(U24-Pad6)") (class "Default")
      (node (ref "U24") (pin "6") (pinfunction "6_6") (pintype "unspecified"))
    )
    (net (code "202") (name "unconnected-(U25-6-Pad7)") (class "Default")
      (node (ref "U25") (pin "7") (pinfunction "6_7") (pintype "unspecified"))
    )
    (net (code "203") (name "unconnected-(U25-Pad6)") (class "Default")
      (node (ref "U25") (pin "6") (pinfunction "6_6") (pintype "unspecified"))
    )
    (net (code "204") (name "unconnected-(U26-6-Pad4)") (class "Default")
      (node (ref "U26") (pin "4") (pinfunction "6_4") (pintype "unspecified"))
    )
    (net (code "205") (name "unconnected-(U26-6-Pad5)") (class "Default")
      (node (ref "U26") (pin "5") (pinfunction "6_5") (pintype "unspecified"))
    )
    (net (code "206") (name "unconnected-(U26-6-Pad7)") (class "Default")
      (node (ref "U26") (pin "7") (pinfunction "6_7") (pintype "unspecified"))
    )
    (net (code "207") (name "unconnected-(U26-Pad6)") (class "Default")
      (node (ref "U26") (pin "6") (pinfunction "6_6") (pintype "unspecified"))
    )
  )
)
